# uOsc_1_v3.net
KiCad netlist of a schematic drawn in EAGLE
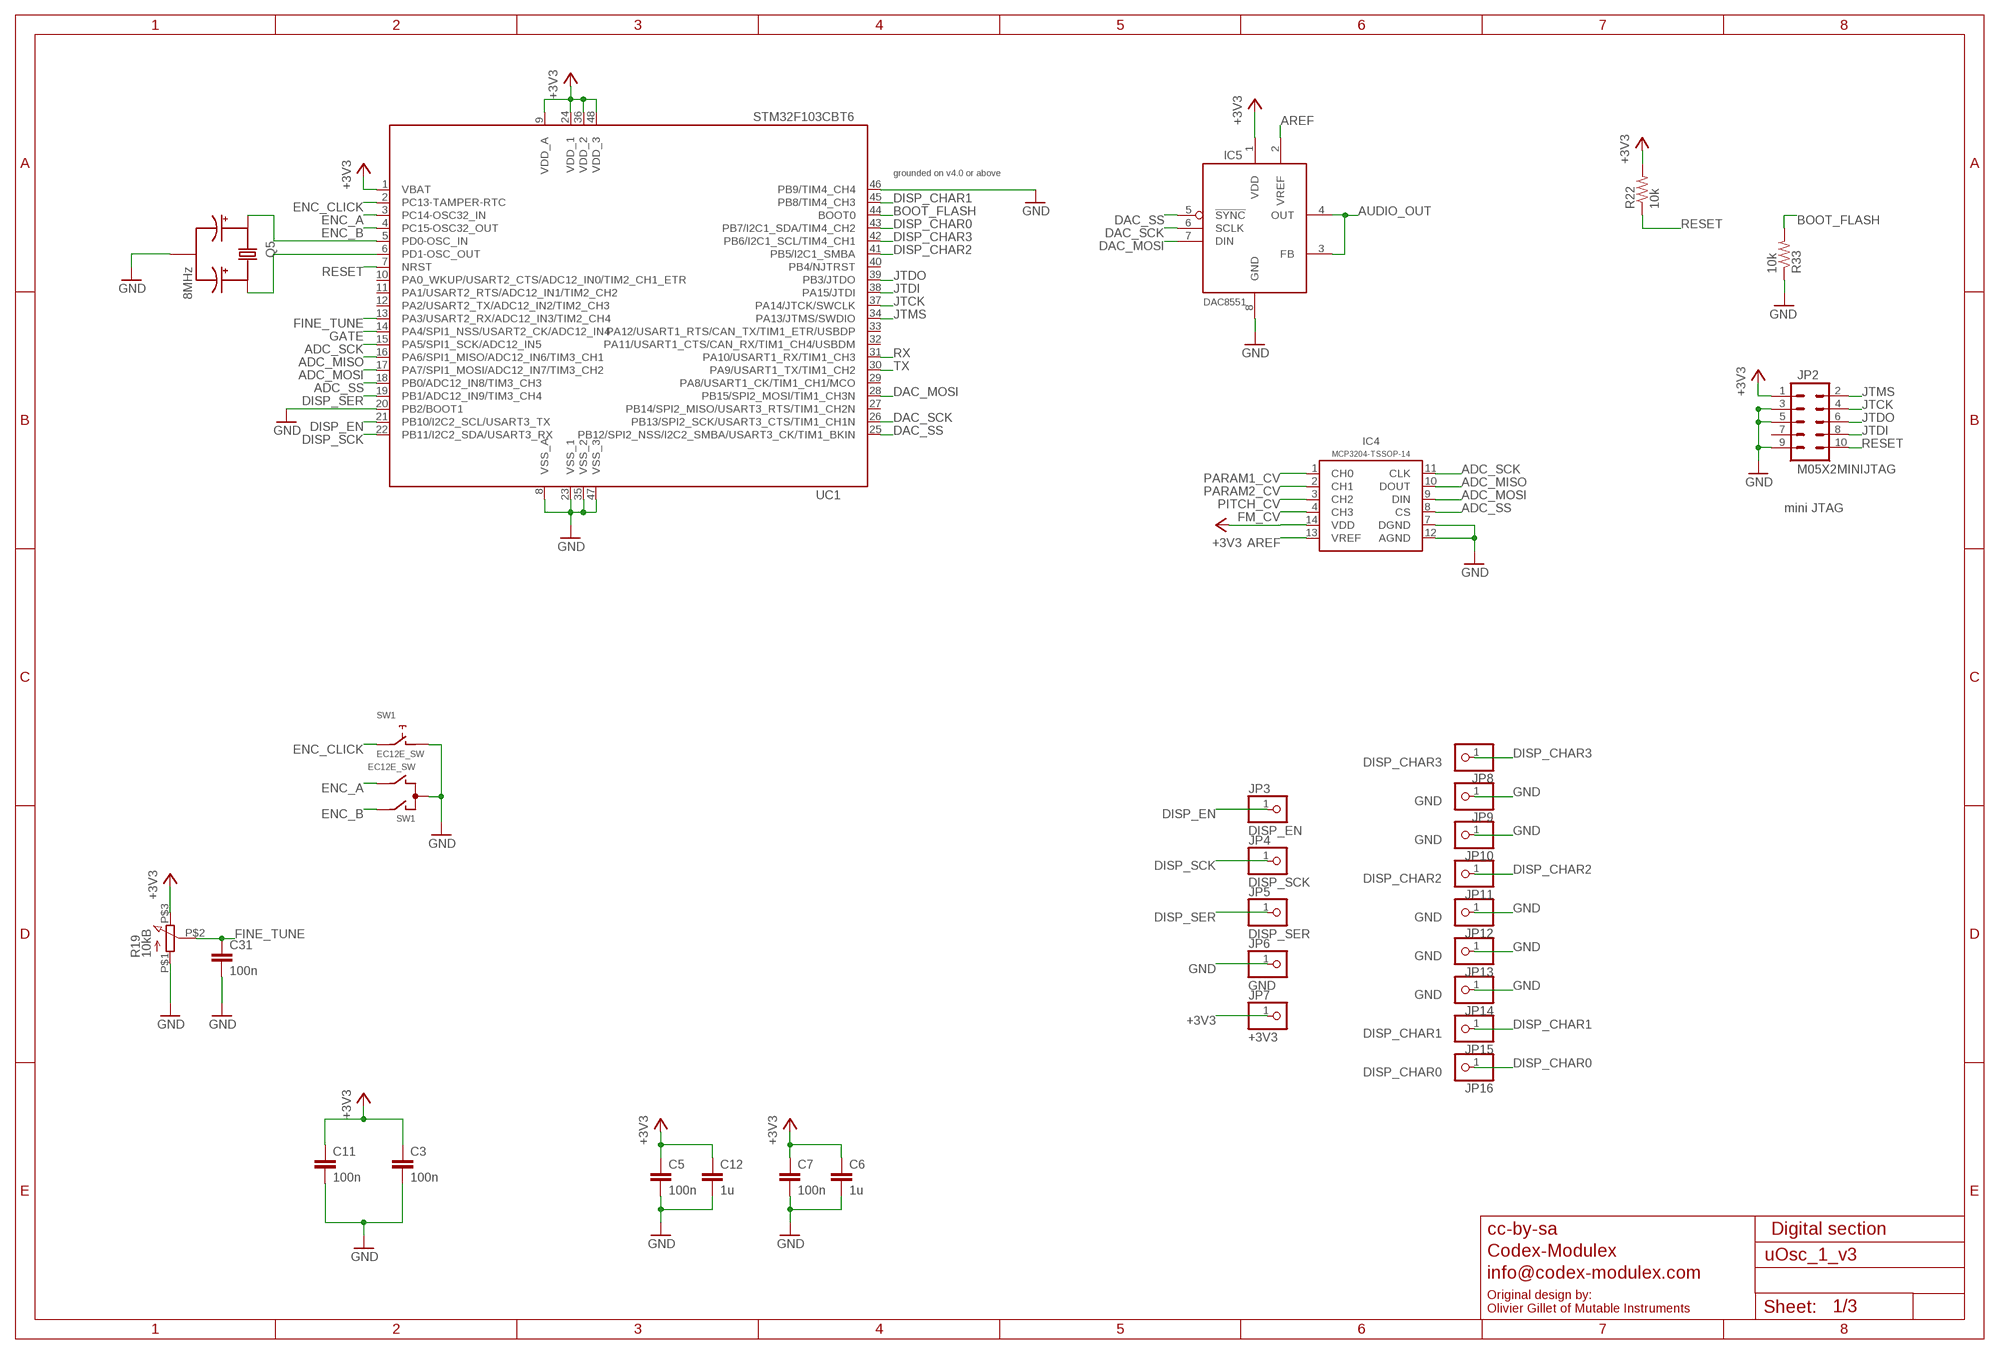
[diagram p0: schematic, sheet 1]
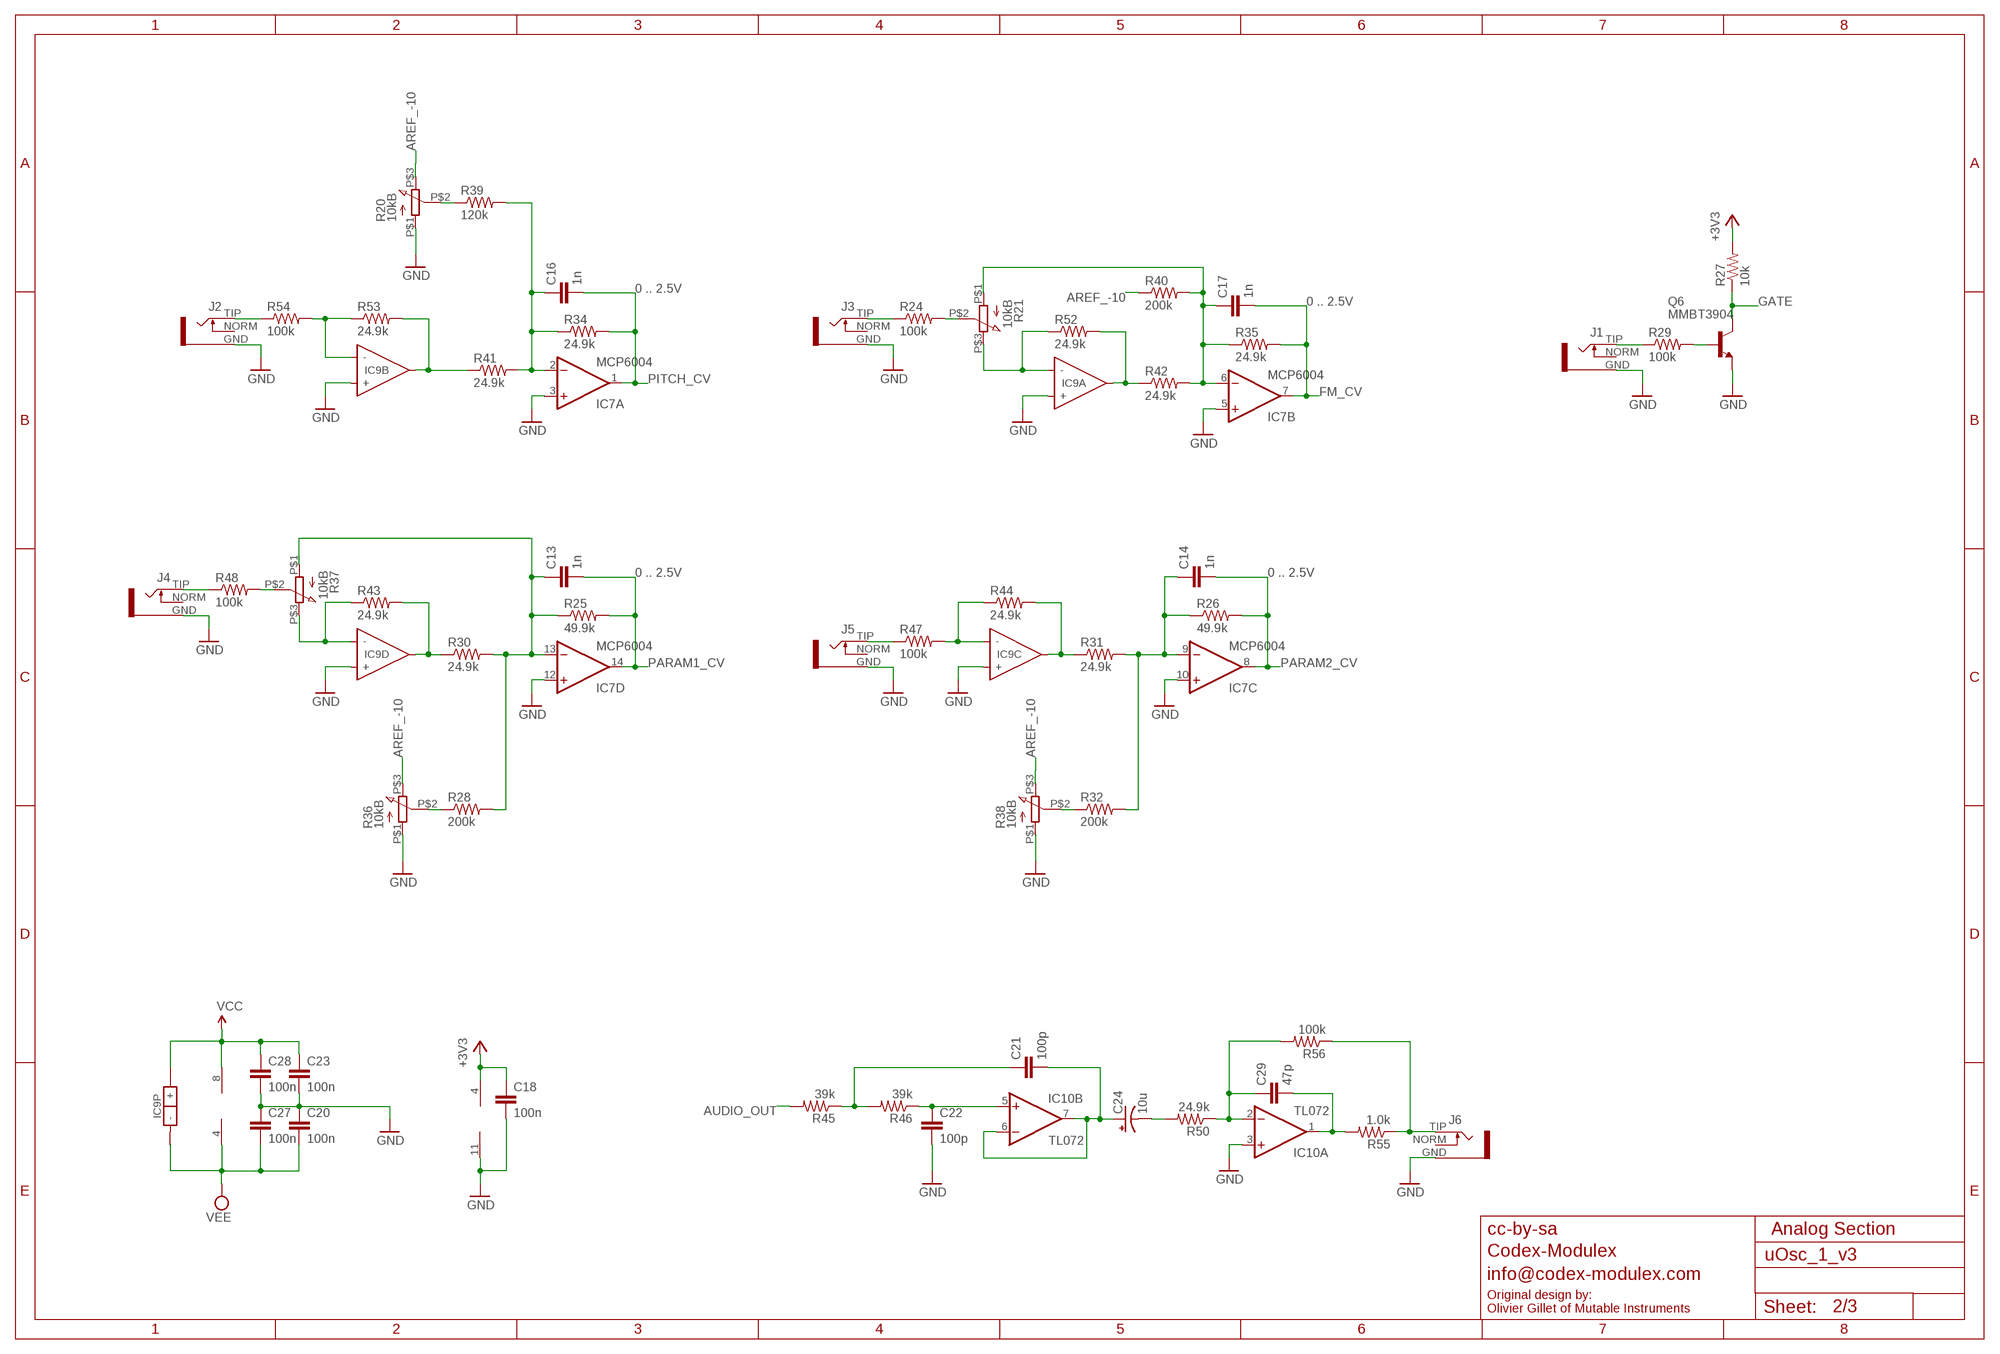
[diagram p1: schematic, sheet 2]
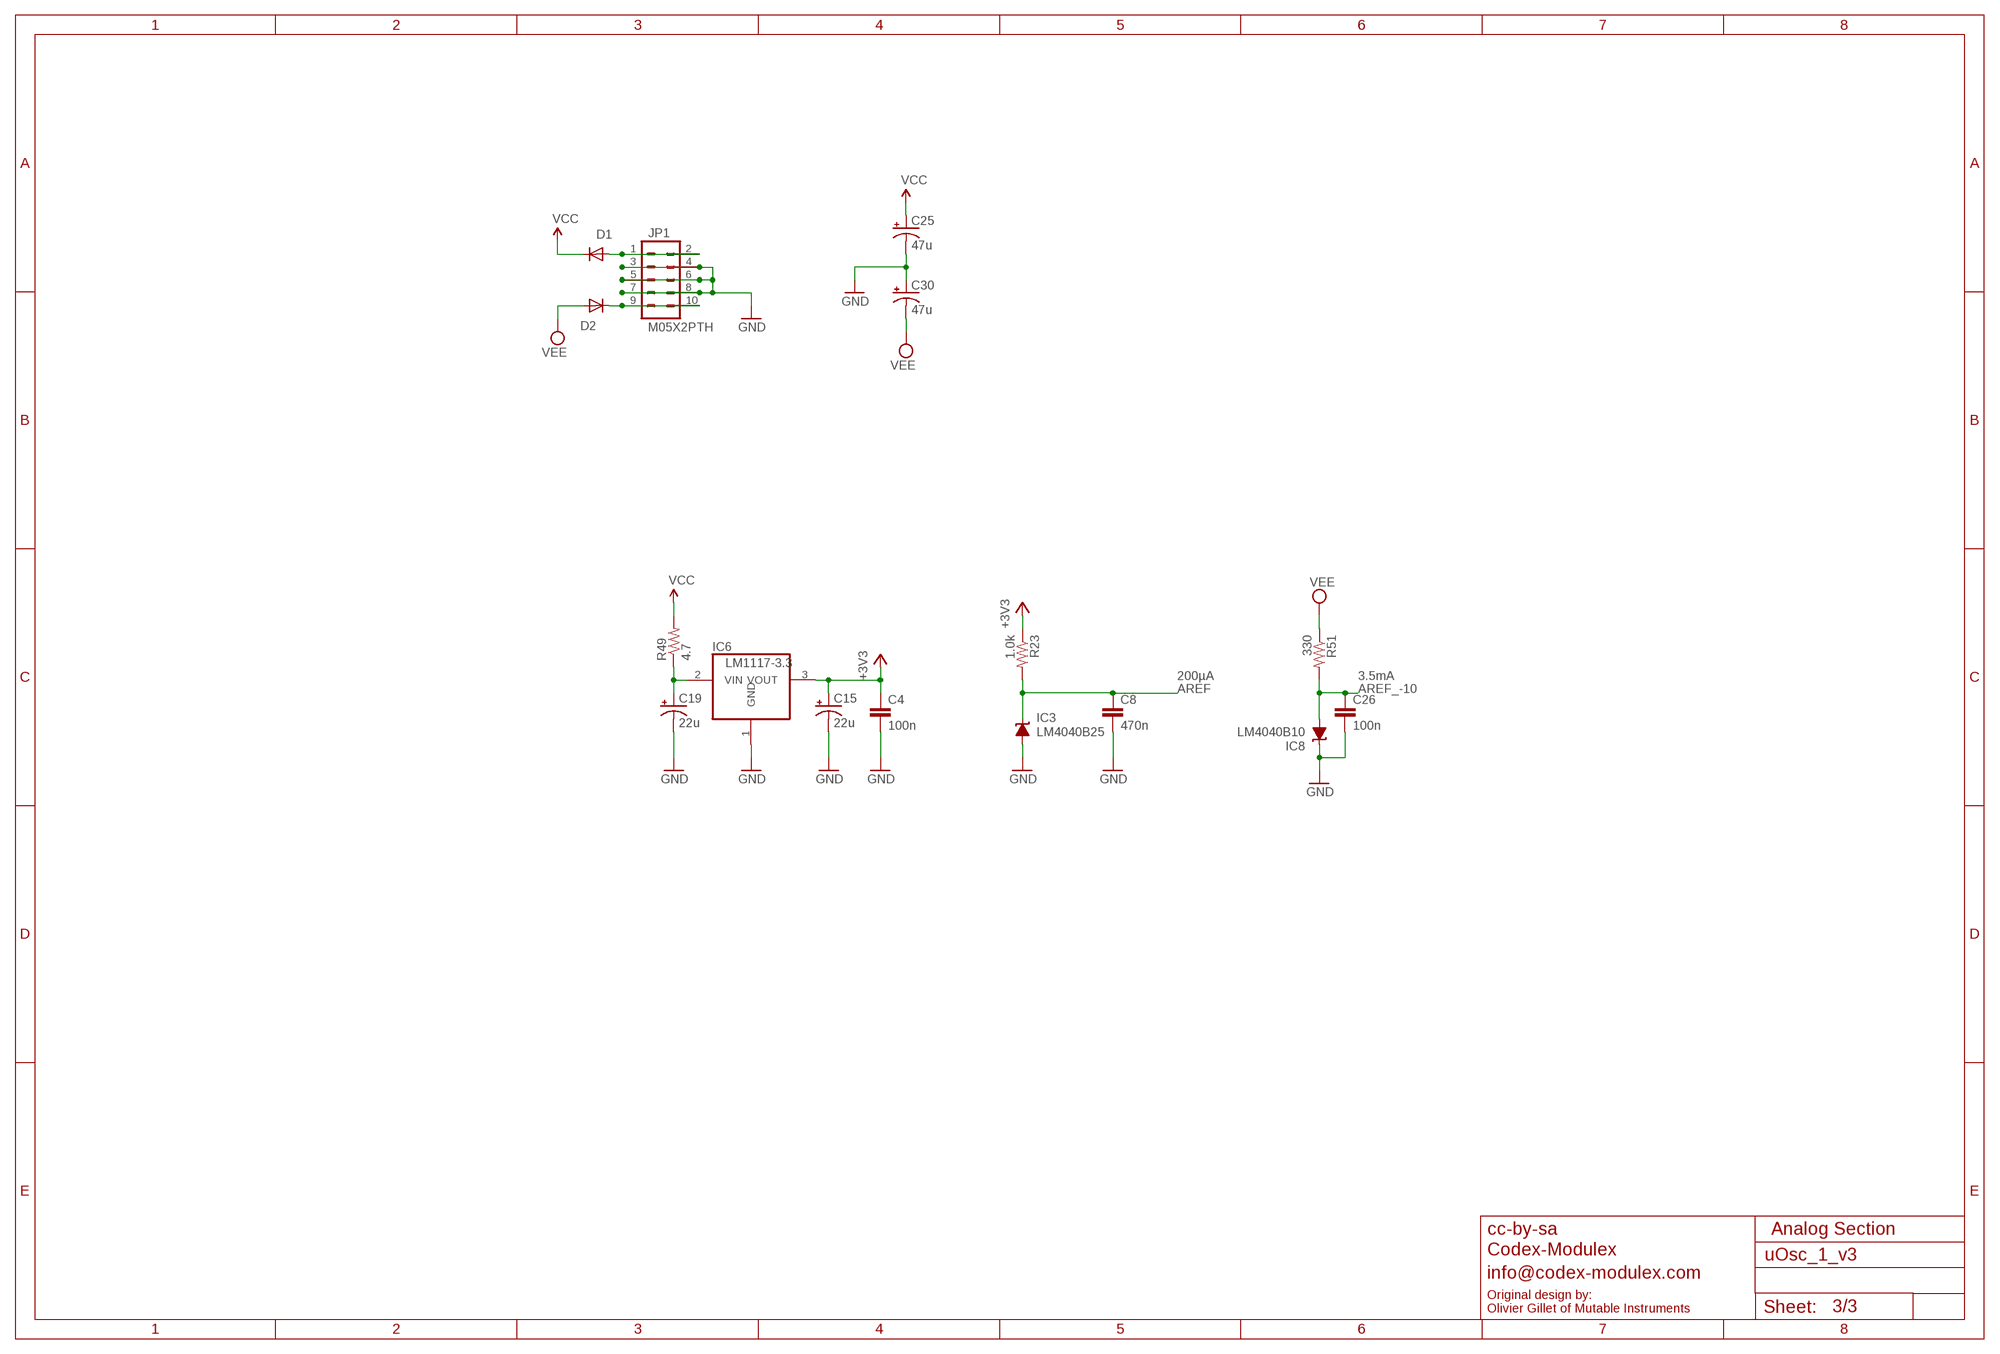
[diagram p2: schematic, sheet 3]

(export (version "E")
  (design (tool "Eeschema 10.0.6"))
  (components
    (comp (ref "C4")
      (value "100n")
      (footprint "eagle-import:PARTS_AMAN_RESISTOR_0603")
      (libsource (lib "eagle-import") (part "PARTS_AMAN_CAPACITOR"))
    )
    (comp (ref "C8")
      (value "470n")
      (footprint "eagle-import:PARTS_AMAN_RESISTOR_0603")
      (libsource (lib "eagle-import") (part "PARTS_AMAN_CAPACITOR"))
    )
    (comp (ref "C15")
      (value "22u")
      (footprint "eagle-import:PANASONIC_C")
      (libsource (lib "eagle-import") (part "CPOL-USC"))
    )
    (comp (ref "C19")
      (value "22u")
      (footprint "eagle-import:PANASONIC_C")
      (libsource (lib "eagle-import") (part "CPOL-USC"))
    )
    (comp (ref "C25")
      (value "47u")
      (footprint "eagle-import:PANASONIC_D")
      (libsource (lib "eagle-import") (part "CPOL-USD"))
    )
    (comp (ref "C26")
      (value "100n")
      (footprint "eagle-import:PARTS_AMAN_RESISTOR_0603")
      (libsource (lib "eagle-import") (part "PARTS_AMAN_CAPACITOR"))
    )
    (comp (ref "C30")
      (value "47u")
      (footprint "eagle-import:PANASONIC_D")
      (libsource (lib "eagle-import") (part "CPOL-USD"))
    )
    (comp (ref "D1")
      (value "1N5819HW")
      (footprint "eagle-import:SOD123")
      (libsource (lib "eagle-import") (part "DIODE-SOD123"))
    )
    (comp (ref "D2")
      (value "1N5819HW")
      (footprint "eagle-import:SOD123")
      (libsource (lib "eagle-import") (part "DIODE-SOD123"))
    )
    (comp (ref "IC3")
      (value "LM4040B25")
      (footprint "eagle-import:DBZ_R-PDSO-G3")
      (libsource (lib "eagle-import") (part "LM4041DBZB12"))
    )
    (comp (ref "IC6")
      (value "LM1117-3.3")
      (footprint "eagle-import:TO252")
      (libsource (lib "eagle-import") (part "REG1117T"))
    )
    (comp (ref "IC8")
      (value "LM4040B10")
      (footprint "eagle-import:DBZ_R-PDSO-G3")
      (libsource (lib "eagle-import") (part "LM4041DBZB12"))
    )
    (comp (ref "JP1")
      (value "M05X2PTH")
      (footprint "eagle-import:AVR_ICSP")
      (libsource (lib "eagle-import") (part "M05X2PTH"))
    )
    (comp (ref "R23")
      (value "1.0k")
      (footprint "eagle-import:PARTS_AMAN_RESISTOR_0603")
      (libsource (lib "eagle-import") (part "PARTS_AMAN_RESISTOR"))
    )
    (comp (ref "R49")
      (value "4.7")
      (footprint "eagle-import:R1206")
      (libsource (lib "eagle-import") (part "R-US_R1206"))
    )
    (comp (ref "R51")
      (value "330")
      (footprint "eagle-import:PARTS_AMAN_RESISTOR_0603")
      (libsource (lib "eagle-import") (part "PARTS_AMAN_RESISTOR"))
    )
    (comp (ref "C3")
      (value "100n")
      (footprint "eagle-import:PARTS_AMAN_RESISTOR_0603")
      (libsource (lib "eagle-import") (part "PARTS_AMAN_CAPACITOR"))
    )
    (comp (ref "C5")
      (value "100n")
      (footprint "eagle-import:PARTS_AMAN_RESISTOR_0603")
      (libsource (lib "eagle-import") (part "PARTS_AMAN_CAPACITOR"))
    )
    (comp (ref "C6")
      (value "1u")
      (footprint "eagle-import:PARTS_AMAN_RESISTOR_0603")
      (libsource (lib "eagle-import") (part "PARTS_AMAN_CAPACITOR"))
    )
    (comp (ref "C7")
      (value "100n")
      (footprint "eagle-import:PARTS_AMAN_RESISTOR_0603")
      (libsource (lib "eagle-import") (part "PARTS_AMAN_CAPACITOR"))
    )
    (comp (ref "C11")
      (value "100n")
      (footprint "eagle-import:PARTS_AMAN_RESISTOR_0603")
      (libsource (lib "eagle-import") (part "PARTS_AMAN_CAPACITOR"))
    )
    (comp (ref "C12")
      (value "1u")
      (footprint "eagle-import:PARTS_AMAN_RESISTOR_0603")
      (libsource (lib "eagle-import") (part "PARTS_AMAN_CAPACITOR"))
    )
    (comp (ref "C31")
      (value "100n")
      (footprint "eagle-import:PARTS_AMAN_RESISTOR_0603")
      (libsource (lib "eagle-import") (part "PARTS_AMAN_CAPACITOR"))
    )
    (comp (ref "IC4")
      (value "MCP3204-TSSOP-14")
      (footprint "eagle-import:UBRAIDS_SE_TSSOP-14")
      (libsource (lib "eagle-import") (part "UBRAIDS_SE_MCP3204-TSSOP-14"))
    )
    (comp (ref "IC5")
      (value "DAC8551")
      (footprint "eagle-import:MSOP-8")
      (libsource (lib "eagle-import") (part "DAC855X"))
    )
    (comp (ref "JP2")
      (value "M05X2MINIJTAG")
      (footprint "eagle-import:2X5-1.27")
      (libsource (lib "eagle-import") (part "M05X2MINIJTAG"))
    )
    (comp (ref "JP3")
      (value "DISP_EN")
      (footprint "eagle-import:PARTS_AMAN_1X01")
      (libsource (lib "eagle-import") (part "PARTS_AMAN_PINHD-1X1"))
    )
    (comp (ref "JP4")
      (value "DISP_SCK")
      (footprint "eagle-import:PARTS_AMAN_1X01")
      (libsource (lib "eagle-import") (part "PARTS_AMAN_PINHD-1X1"))
    )
    (comp (ref "JP5")
      (value "DISP_SER")
      (footprint "eagle-import:PARTS_AMAN_1X01")
      (libsource (lib "eagle-import") (part "PARTS_AMAN_PINHD-1X1"))
    )
    (comp (ref "JP6")
      (value "GND")
      (footprint "eagle-import:PARTS_AMAN_1X01")
      (libsource (lib "eagle-import") (part "PARTS_AMAN_PINHD-1X1"))
    )
    (comp (ref "JP7")
      (value "+3V3")
      (footprint "eagle-import:PARTS_AMAN_1X01")
      (libsource (lib "eagle-import") (part "PARTS_AMAN_PINHD-1X1"))
    )
    (comp (ref "JP8")
      (value "DISP_CHAR3")
      (footprint "eagle-import:PARTS_AMAN_1X01")
      (libsource (lib "eagle-import") (part "PARTS_AMAN_PINHD-1X1"))
    )
    (comp (ref "JP9")
      (value "GND")
      (footprint "eagle-import:PARTS_AMAN_1X01")
      (libsource (lib "eagle-import") (part "PARTS_AMAN_PINHD-1X1"))
    )
    (comp (ref "JP10")
      (value "GND")
      (footprint "eagle-import:PARTS_AMAN_1X01")
      (libsource (lib "eagle-import") (part "PARTS_AMAN_PINHD-1X1"))
    )
    (comp (ref "JP11")
      (value "DISP_CHAR2")
      (footprint "eagle-import:PARTS_AMAN_1X01")
      (libsource (lib "eagle-import") (part "PARTS_AMAN_PINHD-1X1"))
    )
    (comp (ref "JP12")
      (value "GND")
      (footprint "eagle-import:PARTS_AMAN_1X01")
      (libsource (lib "eagle-import") (part "PARTS_AMAN_PINHD-1X1"))
    )
    (comp (ref "JP13")
      (value "GND")
      (footprint "eagle-import:PARTS_AMAN_1X01")
      (libsource (lib "eagle-import") (part "PARTS_AMAN_PINHD-1X1"))
    )
    (comp (ref "JP14")
      (value "GND")
      (footprint "eagle-import:PARTS_AMAN_1X01")
      (libsource (lib "eagle-import") (part "PARTS_AMAN_PINHD-1X1"))
    )
    (comp (ref "JP15")
      (value "DISP_CHAR1")
      (footprint "eagle-import:PARTS_AMAN_1X01")
      (libsource (lib "eagle-import") (part "PARTS_AMAN_PINHD-1X1"))
    )
    (comp (ref "JP16")
      (value "DISP_CHAR0")
      (footprint "eagle-import:PARTS_AMAN_1X01")
      (libsource (lib "eagle-import") (part "PARTS_AMAN_PINHD-1X1"))
    )
    (comp (ref "Q5")
      (value "8MHz")
      (footprint "eagle-import:CRYSTAL_SMALLER")
      (libsource (lib "eagle-import") (part "CRYSTAL_SMALLER"))
    )
    (comp (ref "R19")
      (value "10kB")
      (footprint "eagle-import:Q-POT2")
      (libsource (lib "eagle-import") (part "Q-POT2"))
    )
    (comp (ref "R22")
      (value "10k")
      (footprint "eagle-import:PARTS_AMAN_RESISTOR_0603")
      (libsource (lib "eagle-import") (part "PARTS_AMAN_RESISTOR"))
    )
    (comp (ref "R33")
      (value "10k")
      (footprint "eagle-import:PARTS_AMAN_RESISTOR_0603")
      (libsource (lib "eagle-import") (part "PARTS_AMAN_RESISTOR"))
    )
    (comp (ref "SW1")
      (value "EC12E_SW")
      (footprint "eagle-import:ALPS_EC12E_SW")
      (libsource (lib "eagle-import") (part "EC12E_SW"))
    )
    (comp (ref "UC1")
      (value "STM32F103CBT6")
      (footprint "eagle-import:LQFP48")
      (libsource (lib "eagle-import") (part "STM32F103CB"))
    )
    (comp (ref "C13")
      (value "1n")
      (footprint "eagle-import:PARTS_AMAN_RESISTOR_0603")
      (libsource (lib "eagle-import") (part "PARTS_AMAN_CAPACITOR"))
    )
    (comp (ref "C14")
      (value "1n")
      (footprint "eagle-import:PARTS_AMAN_RESISTOR_0603")
      (libsource (lib "eagle-import") (part "PARTS_AMAN_CAPACITOR"))
    )
    (comp (ref "C16")
      (value "1n")
      (footprint "eagle-import:PARTS_AMAN_RESISTOR_0603")
      (libsource (lib "eagle-import") (part "PARTS_AMAN_CAPACITOR"))
    )
    (comp (ref "C17")
      (value "1n")
      (footprint "eagle-import:PARTS_AMAN_RESISTOR_0603")
      (libsource (lib "eagle-import") (part "PARTS_AMAN_CAPACITOR"))
    )
    (comp (ref "C18")
      (value "100n")
      (footprint "eagle-import:PARTS_AMAN_RESISTOR_0603")
      (libsource (lib "eagle-import") (part "PARTS_AMAN_CAPACITOR"))
    )
    (comp (ref "C20")
      (value "100n")
      (footprint "eagle-import:PARTS_AMAN_RESISTOR_0603")
      (libsource (lib "eagle-import") (part "PARTS_AMAN_CAPACITOR"))
    )
    (comp (ref "C21")
      (value "100p")
      (footprint "eagle-import:PARTS_AMAN_RESISTOR_0603")
      (libsource (lib "eagle-import") (part "PARTS_AMAN_CAPACITOR"))
    )
    (comp (ref "C22")
      (value "100p")
      (footprint "eagle-import:PARTS_AMAN_RESISTOR_0603")
      (libsource (lib "eagle-import") (part "PARTS_AMAN_CAPACITOR"))
    )
    (comp (ref "C23")
      (value "100n")
      (footprint "eagle-import:PARTS_AMAN_RESISTOR_0603")
      (libsource (lib "eagle-import") (part "PARTS_AMAN_CAPACITOR"))
    )
    (comp (ref "C24")
      (value "10u")
      (footprint "eagle-import:PANASONIC_B")
      (libsource (lib "eagle-import") (part "CPOL-USB"))
    )
    (comp (ref "C27")
      (value "100n")
      (footprint "eagle-import:PARTS_AMAN_RESISTOR_0603")
      (libsource (lib "eagle-import") (part "PARTS_AMAN_CAPACITOR"))
    )
    (comp (ref "C28")
      (value "100n")
      (footprint "eagle-import:PARTS_AMAN_RESISTOR_0603")
      (libsource (lib "eagle-import") (part "PARTS_AMAN_CAPACITOR"))
    )
    (comp (ref "C29")
      (value "47p")
      (footprint "eagle-import:PARTS_AMAN_RESISTOR_0603")
      (libsource (lib "eagle-import") (part "PARTS_AMAN_CAPACITOR"))
    )
    (comp (ref "IC7")
      (value "MCP6004")
      (footprint "eagle-import:SO14")
      (libsource (lib "eagle-import") (part "TL074D"))
    )
    (comp (ref "IC9")
      (value "TL074")
      (footprint "eagle-import:UBRAIDS_SE_TSSOP-14")
      (libsource (lib "eagle-import") (part "UBRAIDS_SE_TL074-TSSOP-14"))
    )
    (comp (ref "IC10")
      (value "TL072")
      (footprint "eagle-import:SO08")
      (libsource (lib "eagle-import") (part "TL072D"))
    )
    (comp (ref "J1")
      (value "S_JACK_S2_INV")
      (footprint "eagle-import:S_JACK_S2_INV")
      (libsource (lib "eagle-import") (part "S_JACK_S2_INV"))
    )
    (comp (ref "J2")
      (value "S_JACK_S2_INV")
      (footprint "eagle-import:S_JACK_S2_INV")
      (libsource (lib "eagle-import") (part "S_JACK_S2_INV"))
    )
    (comp (ref "J3")
      (value "S_JACK_S2_INV")
      (footprint "eagle-import:S_JACK_S2_INV")
      (libsource (lib "eagle-import") (part "S_JACK_S2_INV"))
    )
    (comp (ref "J4")
      (value "S_JACK_S2_INV")
      (footprint "eagle-import:S_JACK_S2_INV")
      (libsource (lib "eagle-import") (part "S_JACK_S2_INV"))
    )
    (comp (ref "J5")
      (value "S_JACK_S2_INV")
      (footprint "eagle-import:S_JACK_S2_INV")
      (libsource (lib "eagle-import") (part "S_JACK_S2_INV"))
    )
    (comp (ref "J6")
      (value "S_JACK_S2_INV")
      (footprint "eagle-import:S_JACK_S2_INV")
      (libsource (lib "eagle-import") (part "S_JACK_S2_INV"))
    )
    (comp (ref "Q6")
      (value "MMBT3904")
      (footprint "eagle-import:SOT23-BEC")
      (libsource (lib "eagle-import") (part "-NPN-SOT23-BECMMBT3904LT1"))
    )
    (comp (ref "R20")
      (value "10kB")
      (footprint "eagle-import:Q-POT2")
      (libsource (lib "eagle-import") (part "Q-POT2"))
    )
    (comp (ref "R21")
      (value "10kB")
      (footprint "eagle-import:Q-POT2")
      (libsource (lib "eagle-import") (part "Q-POT2"))
    )
    (comp (ref "R24")
      (value "100k")
      (footprint "eagle-import:PARTS_AMAN_RESISTOR_0603")
      (libsource (lib "eagle-import") (part "PARTS_AMAN_RESISTOR"))
    )
    (comp (ref "R25")
      (value "49.9k")
      (footprint "eagle-import:PARTS_AMAN_RESISTOR_0603")
      (libsource (lib "eagle-import") (part "PARTS_AMAN_RESISTOR"))
    )
    (comp (ref "R26")
      (value "49.9k")
      (footprint "eagle-import:PARTS_AMAN_RESISTOR_0603")
      (libsource (lib "eagle-import") (part "PARTS_AMAN_RESISTOR"))
    )
    (comp (ref "R27")
      (value "10k")
      (footprint "eagle-import:PARTS_AMAN_RESISTOR_0603")
      (libsource (lib "eagle-import") (part "PARTS_AMAN_RESISTOR"))
    )
    (comp (ref "R28")
      (value "200k")
      (footprint "eagle-import:PARTS_AMAN_RESISTOR_0603")
      (libsource (lib "eagle-import") (part "PARTS_AMAN_RESISTOR"))
    )
    (comp (ref "R29")
      (value "100k")
      (footprint "eagle-import:PARTS_AMAN_RESISTOR_0603")
      (libsource (lib "eagle-import") (part "PARTS_AMAN_RESISTOR"))
    )
    (comp (ref "R30")
      (value "24.9k")
      (footprint "eagle-import:PARTS_AMAN_RESISTOR_0603")
      (libsource (lib "eagle-import") (part "PARTS_AMAN_RESISTOR"))
    )
    (comp (ref "R31")
      (value "24.9k")
      (footprint "eagle-import:PARTS_AMAN_RESISTOR_0603")
      (libsource (lib "eagle-import") (part "PARTS_AMAN_RESISTOR"))
    )
    (comp (ref "R32")
      (value "200k")
      (footprint "eagle-import:PARTS_AMAN_RESISTOR_0603")
      (libsource (lib "eagle-import") (part "PARTS_AMAN_RESISTOR"))
    )
    (comp (ref "R34")
      (value "24.9k")
      (footprint "eagle-import:PARTS_AMAN_RESISTOR_0603")
      (libsource (lib "eagle-import") (part "PARTS_AMAN_RESISTOR"))
    )
    (comp (ref "R35")
      (value "24.9k")
      (footprint "eagle-import:PARTS_AMAN_RESISTOR_0603")
      (libsource (lib "eagle-import") (part "PARTS_AMAN_RESISTOR"))
    )
    (comp (ref "R36")
      (value "10kB")
      (footprint "eagle-import:Q-POT2")
      (libsource (lib "eagle-import") (part "Q-POT2"))
    )
    (comp (ref "R37")
      (value "10kB")
      (footprint "eagle-import:Q-POT2")
      (libsource (lib "eagle-import") (part "Q-POT2"))
    )
    (comp (ref "R38")
      (value "10kB")
      (footprint "eagle-import:Q-POT2")
      (libsource (lib "eagle-import") (part "Q-POT2"))
    )
    (comp (ref "R39")
      (value "120k")
      (footprint "eagle-import:PARTS_AMAN_RESISTOR_0603")
      (libsource (lib "eagle-import") (part "PARTS_AMAN_RESISTOR"))
    )
    (comp (ref "R40")
      (value "200k")
      (footprint "eagle-import:PARTS_AMAN_RESISTOR_0603")
      (libsource (lib "eagle-import") (part "PARTS_AMAN_RESISTOR"))
    )
    (comp (ref "R41")
      (value "24.9k")
      (footprint "eagle-import:PARTS_AMAN_RESISTOR_0603")
      (libsource (lib "eagle-import") (part "PARTS_AMAN_RESISTOR"))
    )
    (comp (ref "R42")
      (value "24.9k")
      (footprint "eagle-import:PARTS_AMAN_RESISTOR_0603")
      (libsource (lib "eagle-import") (part "PARTS_AMAN_RESISTOR"))
    )
    (comp (ref "R43")
      (value "24.9k")
      (footprint "eagle-import:PARTS_AMAN_RESISTOR_0603")
      (libsource (lib "eagle-import") (part "PARTS_AMAN_RESISTOR"))
    )
    (comp (ref "R44")
      (value "24.9k")
      (footprint "eagle-import:PARTS_AMAN_RESISTOR_0603")
      (libsource (lib "eagle-import") (part "PARTS_AMAN_RESISTOR"))
    )
    (comp (ref "R45")
      (value "39k")
      (footprint "eagle-import:PARTS_AMAN_RESISTOR_0603")
      (libsource (lib "eagle-import") (part "PARTS_AMAN_RESISTOR"))
    )
    (comp (ref "R46")
      (value "39k")
      (footprint "eagle-import:PARTS_AMAN_RESISTOR_0603")
      (libsource (lib "eagle-import") (part "PARTS_AMAN_RESISTOR"))
    )
    (comp (ref "R47")
      (value "100k")
      (footprint "eagle-import:PARTS_AMAN_RESISTOR_0603")
      (libsource (lib "eagle-import") (part "PARTS_AMAN_RESISTOR"))
    )
    (comp (ref "R48")
      (value "100k")
      (footprint "eagle-import:PARTS_AMAN_RESISTOR_0603")
      (libsource (lib "eagle-import") (part "PARTS_AMAN_RESISTOR"))
    )
    (comp (ref "R50")
      (value "24.9k")
      (footprint "eagle-import:PARTS_AMAN_RESISTOR_0603")
      (libsource (lib "eagle-import") (part "PARTS_AMAN_RESISTOR"))
    )
    (comp (ref "R52")
      (value "24.9k")
      (footprint "eagle-import:PARTS_AMAN_RESISTOR_0603")
      (libsource (lib "eagle-import") (part "PARTS_AMAN_RESISTOR"))
    )
    (comp (ref "R53")
      (value "24.9k")
      (footprint "eagle-import:PARTS_AMAN_RESISTOR_0603")
      (libsource (lib "eagle-import") (part "PARTS_AMAN_RESISTOR"))
    )
    (comp (ref "R54")
      (value "100k")
      (footprint "eagle-import:PARTS_AMAN_RESISTOR_0603")
      (libsource (lib "eagle-import") (part "PARTS_AMAN_RESISTOR"))
    )
    (comp (ref "R55")
      (value "1.0k")
      (footprint "eagle-import:PARTS_AMAN_RESISTOR_0603")
      (libsource (lib "eagle-import") (part "PARTS_AMAN_RESISTOR"))
    )
    (comp (ref "R56")
      (value "100k")
      (footprint "eagle-import:PARTS_AMAN_RESISTOR_0603")
      (libsource (lib "eagle-import") (part "PARTS_AMAN_RESISTOR"))
    )
  )
  (nets
    (net (code "1") (name "+3V3") (class "Default")
      (node (ref "C11") (pin "1") (pinfunction "1_1") (pintype "passive"))
      (node (ref "C12") (pin "1") (pinfunction "1_1") (pintype "passive"))
      (node (ref "C15") (pin "+") (pinfunction "+_+") (pintype "passive"))
      (node (ref "C18") (pin "1") (pinfunction "1_1") (pintype "passive"))
      (node (ref "C3") (pin "1") (pinfunction "1_1") (pintype "passive"))
      (node (ref "C4") (pin "1") (pinfunction "1_1") (pintype "passive"))
      (node (ref "C5") (pin "1") (pinfunction "1_1") (pintype "passive"))
      (node (ref "C6") (pin "1") (pinfunction "1_1") (pintype "passive"))
      (node (ref "C7") (pin "1") (pinfunction "1_1") (pintype "passive"))
      (node (ref "IC4") (pin "14") (pinfunction "VDD_14") (pintype "bidirectional"))
      (node (ref "IC5") (pin "1") (pinfunction "VDD_1") (pintype "power_in"))
      (node (ref "IC6") (pin "3") (pinfunction "VOUT_3") (pintype "output"))
      (node (ref "IC7") (pin "4") (pinfunction "V+_4") (pintype "power_in"))
      (node (ref "JP2") (pin "1") (pinfunction "1_1") (pintype "passive"))
      (node (ref "JP7") (pin "1") (pinfunction "1_1") (pintype "passive"))
      (node (ref "R19") (pin "P$3") (pinfunction "3_P$3") (pintype "passive"))
      (node (ref "R22") (pin "2") (pinfunction "2_2") (pintype "passive"))
      (node (ref "R23") (pin "1") (pinfunction "1_1") (pintype "passive"))
      (node (ref "R27") (pin "2") (pinfunction "2_2") (pintype "passive"))
      (node (ref "UC1") (pin "1") (pinfunction "VBAT_1") (pintype "power_in"))
      (node (ref "UC1") (pin "24") (pinfunction "VDD_1_24") (pintype "power_in"))
      (node (ref "UC1") (pin "36") (pinfunction "VDD_2_36") (pintype "power_in"))
      (node (ref "UC1") (pin "48") (pinfunction "VDD_3_48") (pintype "power_in"))
      (node (ref "UC1") (pin "9") (pinfunction "VDD_A_9") (pintype "power_in"))
    )
    (net (code "2") (name "ADC_MISO") (class "Default")
      (node (ref "IC4") (pin "10") (pinfunction "DOUT_10") (pintype "bidirectional"))
      (node (ref "UC1") (pin "16") (pinfunction "PA6/SPI1_MISO/ADC12_IN6/TIM3_CH1_16") (pintype "bidirectional"))
    )
    (net (code "3") (name "ADC_MOSI") (class "Default")
      (node (ref "IC4") (pin "9") (pinfunction "DIN_9") (pintype "bidirectional"))
      (node (ref "UC1") (pin "17") (pinfunction "PA7/SPI1_MOSI/ADC12_IN7/TIM3_CH2_17") (pintype "bidirectional"))
    )
    (net (code "4") (name "ADC_SCK") (class "Default")
      (node (ref "IC4") (pin "11") (pinfunction "CLK_11") (pintype "bidirectional"))
      (node (ref "UC1") (pin "15") (pinfunction "PA5/SPI1_SCK/ADC12_IN5_15") (pintype "bidirectional"))
    )
    (net (code "5") (name "ADC_SS") (class "Default")
      (node (ref "IC4") (pin "8") (pinfunction "CS_8") (pintype "bidirectional"))
      (node (ref "UC1") (pin "18") (pinfunction "PB0/ADC12_IN8/TIM3_CH3_18") (pintype "bidirectional"))
    )
    (net (code "6") (name "AREF") (class "Default")
      (node (ref "C8") (pin "1") (pinfunction "1_1") (pintype "passive"))
      (node (ref "IC3") (pin "1") (pinfunction "C_1") (pintype "passive"))
      (node (ref "IC4") (pin "13") (pinfunction "VREF_13") (pintype "bidirectional"))
      (node (ref "IC5") (pin "2") (pinfunction "VREF_2") (pintype "power_in"))
      (node (ref "R23") (pin "2") (pinfunction "2_2") (pintype "passive"))
    )
    (net (code "7") (name "AREF_-10") (class "Default")
      (node (ref "C26") (pin "1") (pinfunction "1_1") (pintype "passive"))
      (node (ref "IC8") (pin "2") (pinfunction "A_2") (pintype "passive"))
      (node (ref "R20") (pin "P$3") (pinfunction "3_P$3") (pintype "passive"))
      (node (ref "R36") (pin "P$3") (pinfunction "3_P$3") (pintype "passive"))
      (node (ref "R38") (pin "P$3") (pinfunction "3_P$3") (pintype "passive"))
      (node (ref "R40") (pin "1") (pinfunction "1_1") (pintype "passive"))
      (node (ref "R51") (pin "2") (pinfunction "2_2") (pintype "passive"))
    )
    (net (code "8") (name "AUDIO_OUT") (class "Default")
      (node (ref "IC5") (pin "3") (pinfunction "FB_3") (pintype "input"))
      (node (ref "IC5") (pin "4") (pinfunction "OUT_4") (pintype "output"))
      (node (ref "R45") (pin "2") (pinfunction "2_2") (pintype "passive"))
    )
    (net (code "9") (name "BOOT_FLASH") (class "Default")
      (node (ref "R33") (pin "2") (pinfunction "2_2") (pintype "passive"))
      (node (ref "UC1") (pin "44") (pinfunction "BOOT0_44") (pintype "input"))
    )
    (net (code "10") (name "DAC_MOSI") (class "Default")
      (node (ref "IC5") (pin "7") (pinfunction "DIN_7") (pintype "bidirectional"))
      (node (ref "UC1") (pin "28") (pinfunction "PB15/SPI2_MOSI/TIM1_CH3N_28") (pintype "input"))
    )
    (net (code "11") (name "DAC_SCK") (class "Default")
      (node (ref "IC5") (pin "6") (pinfunction "SCLK_6") (pintype "bidirectional"))
      (node (ref "UC1") (pin "26") (pinfunction "PB13/SPI2_SCK/USART3_CTS/TIM1_CH1N_26") (pintype "input"))
    )
    (net (code "12") (name "DAC_SS") (class "Default")
      (node (ref "IC5") (pin "5") (pinfunction "~{SYNC}_5") (pintype "bidirectional"))
      (node (ref "UC1") (pin "25") (pinfunction "PB12/SPI2_NSS/I2C2_SMBA/USART3_CK/TIM1_BKIN_25") (pintype "input"))
    )
    (net (code "13") (name "DISP_CHAR0") (class "Default")
      (node (ref "JP16") (pin "1") (pinfunction "1_1") (pintype "passive"))
      (node (ref "UC1") (pin "43") (pinfunction "PB7/I2C1_SDA/TIM4_CH2_43") (pintype "bidirectional"))
    )
    (net (code "14") (name "DISP_CHAR1") (class "Default")
      (node (ref "JP15") (pin "1") (pinfunction "1_1") (pintype "passive"))
      (node (ref "UC1") (pin "45") (pinfunction "PB8/TIM4_CH3_45") (pintype "bidirectional"))
    )
    (net (code "15") (name "DISP_CHAR2") (class "Default")
      (node (ref "JP11") (pin "1") (pinfunction "1_1") (pintype "passive"))
      (node (ref "UC1") (pin "41") (pinfunction "PB5/I2C1_SMBA_41") (pintype "input"))
    )
    (net (code "16") (name "DISP_CHAR3") (class "Default")
      (node (ref "JP8") (pin "1") (pinfunction "1_1") (pintype "passive"))
      (node (ref "UC1") (pin "42") (pinfunction "PB6/I2C1_SCL/TIM4_CH1_42") (pintype "input"))
    )
    (net (code "17") (name "DISP_EN") (class "Default")
      (node (ref "JP3") (pin "1") (pinfunction "1_1") (pintype "passive"))
      (node (ref "UC1") (pin "21") (pinfunction "PB10/I2C2_SCL/USART3_TX_21") (pintype "input"))
    )
    (net (code "18") (name "DISP_SCK") (class "Default")
      (node (ref "JP4") (pin "1") (pinfunction "1_1") (pintype "passive"))
      (node (ref "UC1") (pin "22") (pinfunction "PB11/I2C2_SDA/USART3_RX_22") (pintype "input"))
    )
    (net (code "19") (name "DISP_SER") (class "Default")
      (node (ref "JP5") (pin "1") (pinfunction "1_1") (pintype "passive"))
      (node (ref "UC1") (pin "19") (pinfunction "PB1/ADC12_IN9/TIM3_CH4_19") (pintype "bidirectional"))
    )
    (net (code "20") (name "ENC_A") (class "Default")
      (node (ref "SW1") (pin "B") (pinfunction "B_B") (pintype "passive"))
      (node (ref "UC1") (pin "3") (pinfunction "PC14-OSC32_IN_3") (pintype "input"))
    )
    (net (code "21") (name "ENC_B") (class "Default")
      (node (ref "SW1") (pin "A") (pinfunction "A_A") (pintype "passive"))
      (node (ref "UC1") (pin "4") (pinfunction "PC15-OSC32_OUT_4") (pintype "input"))
    )
    (net (code "22") (name "ENC_CLICK") (class "Default")
      (node (ref "SW1") (pin "E") (pinfunction "2_E") (pintype "passive"))
      (node (ref "UC1") (pin "2") (pinfunction "PC13-TAMPER-RTC_2") (pintype "input"))
    )
    (net (code "23") (name "FINE_TUNE") (class "Default")
      (node (ref "C31") (pin "1") (pinfunction "1_1") (pintype "passive"))
      (node (ref "R19") (pin "P$2") (pinfunction "2_P$2") (pintype "passive"))
      (node (ref "UC1") (pin "13") (pinfunction "PA3/USART2_RX/ADC12_IN3/TIM2_CH4_13") (pintype "bidirectional"))
    )
    (net (code "24") (name "FM_CV") (class "Default")
      (node (ref "C17") (pin "2") (pinfunction "2_2") (pintype "passive"))
      (node (ref "IC4") (pin "4") (pinfunction "CH3_4") (pintype "bidirectional"))
      (node (ref "IC7") (pin "7") (pinfunction "OUT_7") (pintype "output"))
      (node (ref "R35") (pin "2") (pinfunction "2_2") (pintype "passive"))
    )
    (net (code "25") (name "GATE") (class "Default")
      (node (ref "Q6") (pin "C") (pinfunction "C_C") (pintype "passive"))
      (node (ref "R27") (pin "1") (pinfunction "1_1") (pintype "passive"))
      (node (ref "UC1") (pin "14") (pinfunction "PA4/SPI1_NSS/USART2_CK/ADC12_IN4_14") (pintype "bidirectional"))
    )
    (net (code "26") (name "GND") (class "Default")
      (node (ref "C11") (pin "2") (pinfunction "2_2") (pintype "passive"))
      (node (ref "C12") (pin "2") (pinfunction "2_2") (pintype "passive"))
      (node (ref "C15") (pin "-") (pinfunction "-_-") (pintype "passive"))
      (node (ref "C18") (pin "2") (pinfunction "2_2") (pintype "passive"))
      (node (ref "C19") (pin "-") (pinfunction "-_-") (pintype "passive"))
      (node (ref "C20") (pin "1") (pinfunction "1_1") (pintype "passive"))
      (node (ref "C22") (pin "2") (pinfunction "2_2") (pintype "passive"))
      (node (ref "C23") (pin "2") (pinfunction "2_2") (pintype "passive"))
      (node (ref "C25") (pin "-") (pinfunction "-_-") (pintype "passive"))
      (node (ref "C26") (pin "2") (pinfunction "2_2") (pintype "passive"))
      (node (ref "C27") (pin "1") (pinfunction "1_1") (pintype "passive"))
      (node (ref "C28") (pin "2") (pinfunction "2_2") (pintype "passive"))
      (node (ref "C3") (pin "2") (pinfunction "2_2") (pintype "passive"))
      (node (ref "C30") (pin "+") (pinfunction "+_+") (pintype "passive"))
      (node (ref "C31") (pin "2") (pinfunction "2_2") (pintype "passive"))
      (node (ref "C4") (pin "2") (pinfunction "2_2") (pintype "passive"))
      (node (ref "C5") (pin "2") (pinfunction "2_2") (pintype "passive"))
      (node (ref "C6") (pin "2") (pinfunction "2_2") (pintype "passive"))
      (node (ref "C7") (pin "2") (pinfunction "2_2") (pintype "passive"))
      (node (ref "C8") (pin "2") (pinfunction "2_2") (pintype "passive"))
      (node (ref "IC10") (pin "3") (pinfunction "+IN_3") (pintype "input"))
      (node (ref "IC3") (pin "2") (pinfunction "A_2") (pintype "passive"))
      (node (ref "IC4") (pin "12") (pinfunction "AGND_12") (pintype "bidirectional"))
      (node (ref "IC4") (pin "7") (pinfunction "DGND_7") (pintype "bidirectional"))
      (node (ref "IC5") (pin "8") (pinfunction "GND_8") (pintype "power_in"))
      (node (ref "IC6") (pin "1") (pinfunction "GND_1") (pintype "power_in"))
      (node (ref "IC7") (pin "10") (pinfunction "+IN_10") (pintype "input"))
      (node (ref "IC7") (pin "11") (pinfunction "V-_11") (pintype "power_in"))
      (node (ref "IC7") (pin "12") (pinfunction "+IN_12") (pintype "input"))
      (node (ref "IC7") (pin "3") (pinfunction "+IN_3") (pintype "input"))
      (node (ref "IC7") (pin "5") (pinfunction "+IN_5") (pintype "input"))
      (node (ref "IC8") (pin "1") (pinfunction "C_1") (pintype "passive"))
      (node (ref "IC9") (pin "10") (pinfunction "+_10") (pintype "input"))
      (node (ref "IC9") (pin "12") (pinfunction "+_12") (pintype "input"))
      (node (ref "IC9") (pin "3") (pinfunction "+_3") (pintype "input"))
      (node (ref "IC9") (pin "5") (pinfunction "+_5") (pintype "input"))
      (node (ref "J1") (pin "GND") (pinfunction "GND_GND") (pintype "passive"))
      (node (ref "J2") (pin "GND") (pinfunction "GND_GND") (pintype "passive"))
      (node (ref "J3") (pin "GND") (pinfunction "GND_GND") (pintype "passive"))
      (node (ref "J4") (pin "GND") (pinfunction "GND_GND") (pintype "passive"))
      (node (ref "J5") (pin "GND") (pinfunction "GND_GND") (pintype "passive"))
      (node (ref "J6") (pin "GND") (pinfunction "GND_GND") (pintype "passive"))
      (node (ref "JP1") (pin "3") (pinfunction "3_3") (pintype "passive"))
      (node (ref "JP1") (pin "4") (pinfunction "4_4") (pintype "passive"))
      (node (ref "JP1") (pin "5") (pinfunction "5_5") (pintype "passive"))
      (node (ref "JP1") (pin "6") (pinfunction "6_6") (pintype "passive"))
      (node (ref "JP1") (pin "7") (pinfunction "7_7") (pintype "passive"))
      (node (ref "JP1") (pin "8") (pinfunction "8_8") (pintype "passive"))
      (node (ref "JP10") (pin "1") (pinfunction "1_1") (pintype "passive"))
      (node (ref "JP12") (pin "1") (pinfunction "1_1") (pintype "passive"))
      (node (ref "JP13") (pin "1") (pinfunction "1_1") (pintype "passive"))
      (node (ref "JP14") (pin "1") (pinfunction "1_1") (pintype "passive"))
      (node (ref "JP2") (pin "3") (pinfunction "3_3") (pintype "passive"))
      (node (ref "JP2") (pin "5") (pinfunction "5_5") (pintype "passive"))
      (node (ref "JP2") (pin "9") (pinfunction "9_9") (pintype "passive"))
      (node (ref "JP6") (pin "1") (pinfunction "1_1") (pintype "passive"))
      (node (ref "JP9") (pin "1") (pinfunction "1_1") (pintype "passive"))
      (node (ref "Q5") (pin "GND") (pinfunction "GND_GND") (pintype "bidirectional"))
      (node (ref "Q6") (pin "E") (pinfunction "E_E") (pintype "passive"))
      (node (ref "R19") (pin "P$1") (pinfunction "1_P$1") (pintype "passive"))
      (node (ref "R20") (pin "P$1") (pinfunction "1_P$1") (pintype "passive"))
      (node (ref "R33") (pin "1") (pinfunction "1_1") (pintype "passive"))
      (node (ref "R36") (pin "P$1") (pinfunction "1_P$1") (pintype "passive"))
      (node (ref "R38") (pin "P$1") (pinfunction "1_P$1") (pintype "passive"))
      (node (ref "SW1") (pin "C") (pinfunction "C_C") (pintype "passive"))
      (node (ref "SW1") (pin "D") (pinfunction "1_D") (pintype "passive"))
      (node (ref "UC1") (pin "20") (pinfunction "PB2/BOOT1_20") (pintype "bidirectional"))
      (node (ref "UC1") (pin "23") (pinfunction "VSS_1_23") (pintype "power_in"))
      (node (ref "UC1") (pin "35") (pinfunction "VSS_2_35") (pintype "power_in"))
      (node (ref "UC1") (pin "46") (pinfunction "PB9/TIM4_CH4_46") (pintype "input"))
      (node (ref "UC1") (pin "47") (pinfunction "VSS_3_47") (pintype "power_in"))
      (node (ref "UC1") (pin "8") (pinfunction "VSS_A_8") (pintype "power_in"))
    )
    (net (code "27") (name "JTCK") (class "Default")
      (node (ref "JP2") (pin "4") (pinfunction "4_4") (pintype "passive"))
      (node (ref "UC1") (pin "37") (pinfunction "PA14/JTCK/SWCLK_37") (pintype "bidirectional"))
    )
    (net (code "28") (name "JTDI") (class "Default")
      (node (ref "JP2") (pin "8") (pinfunction "8_8") (pintype "passive"))
      (node (ref "UC1") (pin "38") (pinfunction "PA15/JTDI_38") (pintype "bidirectional"))
    )
    (net (code "29") (name "JTDO") (class "Default")
      (node (ref "JP2") (pin "6") (pinfunction "6_6") (pintype "passive"))
      (node (ref "UC1") (pin "39") (pinfunction "PB3/JTDO_39") (pintype "bidirectional"))
    )
    (net (code "30") (name "JTMS") (class "Default")
      (node (ref "JP2") (pin "2") (pinfunction "2_2") (pintype "passive"))
      (node (ref "UC1") (pin "34") (pinfunction "PA13/JTMS/SWDIO_34") (pintype "bidirectional"))
    )
    (net (code "31") (name "Net-(C21-Pad1)") (class "Default")
      (node (ref "C21") (pin "1") (pinfunction "1_1") (pintype "passive"))
      (node (ref "R45") (pin "1") (pinfunction "1_1") (pintype "passive"))
      (node (ref "R46") (pin "2") (pinfunction "2_2") (pintype "passive"))
    )
    (net (code "32") (name "Net-(C24-Pad-)") (class "Default")
      (node (ref "C24") (pin "-") (pinfunction "-_-") (pintype "passive"))
      (node (ref "R50") (pin "2") (pinfunction "2_2") (pintype "passive"))
    )
    (net (code "33") (name "Net-(D1-PadA)") (class "Default")
      (node (ref "D1") (pin "A") (pinfunction "A_A") (pintype "passive"))
      (node (ref "JP1") (pin "1") (pinfunction "1_1") (pintype "passive"))
      (node (ref "JP1") (pin "2") (pinfunction "2_2") (pintype "passive"))
    )
    (net (code "34") (name "Net-(D2-PadC)") (class "Default")
      (node (ref "D2") (pin "C") (pinfunction "C_C") (pintype "passive"))
      (node (ref "JP1") (pin "10") (pinfunction "10_10") (pintype "passive"))
      (node (ref "JP1") (pin "9") (pinfunction "9_9") (pintype "passive"))
    )
    (net (code "35") (name "Net-(IC6-VIN)") (class "Default")
      (node (ref "C19") (pin "+") (pinfunction "+_+") (pintype "passive"))
      (node (ref "IC6") (pin "2") (pinfunction "VIN_2") (pintype "input"))
      (node (ref "R49") (pin "1") (pinfunction "1_1") (pintype "passive"))
    )
    (net (code "36") (name "Net-(IC7A--IN)") (class "Default")
      (node (ref "C16") (pin "1") (pinfunction "1_1") (pintype "passive"))
      (node (ref "IC7") (pin "2") (pinfunction "-IN_2") (pintype "input"))
      (node (ref "R34") (pin "1") (pinfunction "1_1") (pintype "passive"))
      (node (ref "R39") (pin "2") (pinfunction "2_2") (pintype "passive"))
      (node (ref "R41") (pin "2") (pinfunction "2_2") (pintype "passive"))
    )
    (net (code "37") (name "Net-(IC7B--IN)") (class "Default")
      (node (ref "C17") (pin "1") (pinfunction "1_1") (pintype "passive"))
      (node (ref "IC7") (pin "6") (pinfunction "-IN_6") (pintype "input"))
      (node (ref "R21") (pin "P$1") (pinfunction "1_P$1") (pintype "passive"))
      (node (ref "R35") (pin "1") (pinfunction "1_1") (pintype "passive"))
      (node (ref "R40") (pin "2") (pinfunction "2_2") (pintype "passive"))
      (node (ref "R42") (pin "2") (pinfunction "2_2") (pintype "passive"))
    )
    (net (code "38") (name "Net-(IC7C--IN)") (class "Default")
      (node (ref "C14") (pin "1") (pinfunction "1_1") (pintype "passive"))
      (node (ref "IC7") (pin "9") (pinfunction "-IN_9") (pintype "input"))
      (node (ref "R26") (pin "1") (pinfunction "1_1") (pintype "passive"))
      (node (ref "R31") (pin "2") (pinfunction "2_2") (pintype "passive"))
      (node (ref "R32") (pin "2") (pinfunction "2_2") (pintype "passive"))
    )
    (net (code "39") (name "Net-(IC7D--IN)") (class "Default")
      (node (ref "C13") (pin "1") (pinfunction "1_1") (pintype "passive"))
      (node (ref "IC7") (pin "13") (pinfunction "-IN_13") (pintype "input"))
      (node (ref "R25") (pin "1") (pinfunction "1_1") (pintype "passive"))
      (node (ref "R28") (pin "2") (pinfunction "2_2") (pintype "passive"))
      (node (ref "R30") (pin "2") (pinfunction "2_2") (pintype "passive"))
      (node (ref "R37") (pin "P$1") (pinfunction "1_P$1") (pintype "passive"))
    )
    (net (code "40") (name "Net-(IC9A--)") (class "Default")
      (node (ref "IC9") (pin "2") (pinfunction "-_2") (pintype "input"))
      (node (ref "R21") (pin "P$3") (pinfunction "3_P$3") (pintype "passive"))
      (node (ref "R52") (pin "1") (pinfunction "1_1") (pintype "passive"))
    )
    (net (code "41") (name "Net-(IC9A-OUT)") (class "Default")
      (node (ref "IC9") (pin "1") (pinfunction "OUT_1") (pintype "output"))
      (node (ref "R42") (pin "1") (pinfunction "1_1") (pintype "passive"))
      (node (ref "R52") (pin "2") (pinfunction "2_2") (pintype "passive"))
    )
    (net (code "42") (name "Net-(IC9B--)") (class "Default")
      (node (ref "IC9") (pin "6") (pinfunction "-_6") (pintype "input"))
      (node (ref "R53") (pin "1") (pinfunction "1_1") (pintype "passive"))
      (node (ref "R54") (pin "2") (pinfunction "2_2") (pintype "passive"))
    )
    (net (code "43") (name "Net-(IC9B-OUT)") (class "Default")
      (node (ref "IC9") (pin "7") (pinfunction "OUT_7") (pintype "output"))
      (node (ref "R41") (pin "1") (pinfunction "1_1") (pintype "passive"))
      (node (ref "R53") (pin "2") (pinfunction "2_2") (pintype "passive"))
    )
    (net (code "44") (name "Net-(IC9C--)") (class "Default")
      (node (ref "IC9") (pin "9") (pinfunction "-_9") (pintype "input"))
      (node (ref "R44") (pin "1") (pinfunction "1_1") (pintype "passive"))
      (node (ref "R47") (pin "2") (pinfunction "2_2") (pintype "passive"))
    )
    (net (code "45") (name "Net-(IC9C-OUT)") (class "Default")
      (node (ref "IC9") (pin "8") (pinfunction "OUT_8") (pintype "output"))
      (node (ref "R31") (pin "1") (pinfunction "1_1") (pintype "passive"))
      (node (ref "R44") (pin "2") (pinfunction "2_2") (pintype "passive"))
    )
    (net (code "46") (name "Net-(IC9D--)") (class "Default")
      (node (ref "IC9") (pin "13") (pinfunction "-_13") (pintype "input"))
      (node (ref "R37") (pin "P$3") (pinfunction "3_P$3") (pintype "passive"))
      (node (ref "R43") (pin "1") (pinfunction "1_1") (pintype "passive"))
    )
    (net (code "47") (name "Net-(IC9D-OUT)") (class "Default")
      (node (ref "IC9") (pin "14") (pinfunction "OUT_14") (pintype "output"))
      (node (ref "R30") (pin "1") (pinfunction "1_1") (pintype "passive"))
      (node (ref "R43") (pin "2") (pinfunction "2_2") (pintype "passive"))
    )
    (net (code "48") (name "Net-(IC10A--IN)") (class "Default")
      (node (ref "C29") (pin "1") (pinfunction "1_1") (pintype "passive"))
      (node (ref "IC10") (pin "2") (pinfunction "-IN_2") (pintype "input"))
      (node (ref "R50") (pin "1") (pinfunction "1_1") (pintype "passive"))
      (node (ref "R56") (pin "2") (pinfunction "2_2") (pintype "passive"))
    )
    (net (code "49") (name "Net-(IC10A-OUT)") (class "Default")
      (node (ref "C29") (pin "2") (pinfunction "2_2") (pintype "passive"))
      (node (ref "IC10") (pin "1") (pinfunction "OUT_1") (pintype "output"))
      (node (ref "R55") (pin "2") (pinfunction "2_2") (pintype "passive"))
    )
    (net (code "50") (name "Net-(IC10B-+IN)") (class "Default")
      (node (ref "C22") (pin "1") (pinfunction "1_1") (pintype "passive"))
      (node (ref "IC10") (pin "5") (pinfunction "+IN_5") (pintype "input"))
      (node (ref "R46") (pin "1") (pinfunction "1_1") (pintype "passive"))
    )
    (net (code "51") (name "Net-(IC10B--IN)") (class "Default")
      (node (ref "C21") (pin "2") (pinfunction "2_2") (pintype "passive"))
      (node (ref "C24") (pin "+") (pinfunction "+_+") (pintype "passive"))
      (node (ref "IC10") (pin "6") (pinfunction "-IN_6") (pintype "input"))
      (node (ref "IC10") (pin "7") (pinfunction "OUT_7") (pintype "output"))
    )
    (net (code "52") (name "Net-(J1-PadTIP)") (class "Default")
      (node (ref "J1") (pin "TIP") (pinfunction "TIP_TIP") (pintype "passive"))
      (node (ref "R29") (pin "1") (pinfunction "1_1") (pintype "passive"))
    )
    (net (code "53") (name "Net-(J2-PadTIP)") (class "Default")
      (node (ref "J2") (pin "TIP") (pinfunction "TIP_TIP") (pintype "passive"))
      (node (ref "R54") (pin "1") (pinfunction "1_1") (pintype "passive"))
    )
    (net (code "54") (name "Net-(J3-PadTIP)") (class "Default")
      (node (ref "J3") (pin "TIP") (pinfunction "TIP_TIP") (pintype "passive"))
      (node (ref "R24") (pin "1") (pinfunction "1_1") (pintype "passive"))
    )
    (net (code "55") (name "Net-(J4-PadTIP)") (class "Default")
      (node (ref "J4") (pin "TIP") (pinfunction "TIP_TIP") (pintype "passive"))
      (node (ref "R48") (pin "1") (pinfunction "1_1") (pintype "passive"))
    )
    (net (code "56") (name "Net-(J5-PadTIP)") (class "Default")
      (node (ref "J5") (pin "TIP") (pinfunction "TIP_TIP") (pintype "passive"))
      (node (ref "R47") (pin "1") (pinfunction "1_1") (pintype "passive"))
    )
    (net (code "57") (name "Net-(J6-PadTIP)") (class "Default")
      (node (ref "J6") (pin "TIP") (pinfunction "TIP_TIP") (pintype "passive"))
      (node (ref "R55") (pin "1") (pinfunction "1_1") (pintype "passive"))
      (node (ref "R56") (pin "1") (pinfunction "1_1") (pintype "passive"))
    )
    (net (code "58") (name "Net-(Q6-PadB)") (class "Default")
      (node (ref "Q6") (pin "B") (pinfunction "B_B") (pintype "passive"))
      (node (ref "R29") (pin "2") (pinfunction "2_2") (pintype "passive"))
    )
    (net (code "59") (name "Net-(R20-2)") (class "Default")
      (node (ref "R20") (pin "P$2") (pinfunction "2_P$2") (pintype "passive"))
      (node (ref "R39") (pin "1") (pinfunction "1_1") (pintype "passive"))
    )
    (net (code "60") (name "Net-(R21-2)") (class "Default")
      (node (ref "R21") (pin "P$2") (pinfunction "2_P$2") (pintype "passive"))
      (node (ref "R24") (pin "2") (pinfunction "2_2") (pintype "passive"))
    )
    (net (code "61") (name "Net-(R36-2)") (class "Default")
      (node (ref "R28") (pin "1") (pinfunction "1_1") (pintype "passive"))
      (node (ref "R36") (pin "P$2") (pinfunction "2_P$2") (pintype "passive"))
    )
    (net (code "62") (name "Net-(R37-2)") (class "Default")
      (node (ref "R37") (pin "P$2") (pinfunction "2_P$2") (pintype "passive"))
      (node (ref "R48") (pin "2") (pinfunction "2_2") (pintype "passive"))
    )
    (net (code "63") (name "Net-(R38-2)") (class "Default")
      (node (ref "R32") (pin "1") (pinfunction "1_1") (pintype "passive"))
      (node (ref "R38") (pin "P$2") (pinfunction "2_P$2") (pintype "passive"))
    )
    (net (code "64") (name "Net-(UC1-PD0-OSC_IN)") (class "Default")
      (node (ref "Q5") (pin "X1") (pinfunction "X1_X1") (pintype "bidirectional"))
      (node (ref "UC1") (pin "5") (pinfunction "PD0-OSC_IN_5") (pintype "input"))
    )
    (net (code "65") (name "Net-(UC1-PD1-OSC_OUT)") (class "Default")
      (node (ref "Q5") (pin "X2") (pinfunction "X2_X2") (pintype "bidirectional"))
      (node (ref "UC1") (pin "6") (pinfunction "PD1-OSC_OUT_6") (pintype "input"))
    )
    (net (code "66") (name "PARAM1_CV") (class "Default")
      (node (ref "C13") (pin "2") (pinfunction "2_2") (pintype "passive"))
      (node (ref "IC4") (pin "1") (pinfunction "CH0_1") (pintype "bidirectional"))
      (node (ref "IC7") (pin "14") (pinfunction "OUT_14") (pintype "output"))
      (node (ref "R25") (pin "2") (pinfunction "2_2") (pintype "passive"))
    )
    (net (code "67") (name "PARAM2_CV") (class "Default")
      (node (ref "C14") (pin "2") (pinfunction "2_2") (pintype "passive"))
      (node (ref "IC4") (pin "2") (pinfunction "CH1_2") (pintype "bidirectional"))
      (node (ref "IC7") (pin "8") (pinfunction "OUT_8") (pintype "output"))
      (node (ref "R26") (pin "2") (pinfunction "2_2") (pintype "passive"))
    )
    (net (code "68") (name "PITCH_CV") (class "Default")
      (node (ref "C16") (pin "2") (pinfunction "2_2") (pintype "passive"))
      (node (ref "IC4") (pin "3") (pinfunction "CH2_3") (pintype "bidirectional"))
      (node (ref "IC7") (pin "1") (pinfunction "OUT_1") (pintype "output"))
      (node (ref "R34") (pin "2") (pinfunction "2_2") (pintype "passive"))
    )
    (net (code "69") (name "RESET") (class "Default")
      (node (ref "JP2") (pin "10") (pinfunction "10_10") (pintype "passive"))
      (node (ref "R22") (pin "1") (pinfunction "1_1") (pintype "passive"))
      (node (ref "UC1") (pin "7") (pinfunction "NRST_7") (pintype "input"))
    )
    (net (code "70") (name "RX") (class "Default")
      (node (ref "UC1") (pin "31") (pinfunction "PA10/USART1_RX/TIM1_CH3_31") (pintype "bidirectional"))
    )
    (net (code "71") (name "TX") (class "Default")
      (node (ref "UC1") (pin "30") (pinfunction "PA9/USART1_TX/TIM1_CH2_30") (pintype "input"))
    )
    (net (code "72") (name "VCC") (class "Default")
      (node (ref "C23") (pin "1") (pinfunction "1_1") (pintype "passive"))
      (node (ref "C25") (pin "+") (pinfunction "+_+") (pintype "passive"))
      (node (ref "C28") (pin "1") (pinfunction "1_1") (pintype "passive"))
      (node (ref "D1") (pin "C") (pinfunction "C_C") (pintype "passive"))
      (node (ref "IC10") (pin "8") (pinfunction "V+_8") (pintype "power_in"))
      (node (ref "IC9") (pin "4") (pinfunction "+_4") (pintype "bidirectional"))
      (node (ref "R49") (pin "2") (pinfunction "2_2") (pintype "passive"))
    )
    (net (code "73") (name "VEE") (class "Default")
      (node (ref "C20") (pin "2") (pinfunction "2_2") (pintype "passive"))
      (node (ref "C27") (pin "2") (pinfunction "2_2") (pintype "passive"))
      (node (ref "C30") (pin "-") (pinfunction "-_-") (pintype "passive"))
      (node (ref "D2") (pin "A") (pinfunction "A_A") (pintype "passive"))
      (node (ref "IC10") (pin "4") (pinfunction "V-_4") (pintype "power_in"))
      (node (ref "IC9") (pin "11") (pinfunction "-_11") (pintype "bidirectional"))
      (node (ref "R51") (pin "1") (pinfunction "1_1") (pintype "passive"))
    )
    (net (code "74") (name "unconnected-(J1-PadNORM)") (class "Default")
      (node (ref "J1") (pin "NORM") (pinfunction "NORM_NORM") (pintype "passive"))
    )
    (net (code "75") (name "unconnected-(J2-PadNORM)") (class "Default")
      (node (ref "J2") (pin "NORM") (pinfunction "NORM_NORM") (pintype "passive"))
    )
    (net (code "76") (name "unconnected-(J3-PadNORM)") (class "Default")
      (node (ref "J3") (pin "NORM") (pinfunction "NORM_NORM") (pintype "passive"))
    )
    (net (code "77") (name "unconnected-(J4-PadNORM)") (class "Default")
      (node (ref "J4") (pin "NORM") (pinfunction "NORM_NORM") (pintype "passive"))
    )
    (net (code "78") (name "unconnected-(J5-PadNORM)") (class "Default")
      (node (ref "J5") (pin "NORM") (pinfunction "NORM_NORM") (pintype "passive"))
    )
    (net (code "79") (name "unconnected-(J6-PadNORM)") (class "Default")
      (node (ref "J6") (pin "NORM") (pinfunction "NORM_NORM") (pintype "passive"))
    )
    (net (code "80") (name "unconnected-(JP2-Pad7)") (class "Default")
      (node (ref "JP2") (pin "7") (pinfunction "7_7") (pintype "passive"))
    )
    (net (code "81") (name "unconnected-(UC1-PA0_WKUP{slash}USART2_CTS{slash}ADC12_IN0{slash}TIM2_CH1_ETR-Pad10)") (class "Default")
      (node (ref "UC1") (pin "10") (pinfunction "PA0_WKUP/USART2_CTS/ADC12_IN0/TIM2_CH1_ETR_10") (pintype "bidirectional"))
    )
    (net (code "82") (name "unconnected-(UC1-PA1{slash}USART2_RTS{slash}ADC12_IN1{slash}TIM2_CH2-Pad11)") (class "Default")
      (node (ref "UC1") (pin "11") (pinfunction "PA1/USART2_RTS/ADC12_IN1/TIM2_CH2_11") (pintype "bidirectional"))
    )
    (net (code "83") (name "unconnected-(UC1-PA2{slash}USART2_TX{slash}ADC12_IN2{slash}TIM2_CH3-Pad12)") (class "Default")
      (node (ref "UC1") (pin "12") (pinfunction "PA2/USART2_TX/ADC12_IN2/TIM2_CH3_12") (pintype "bidirectional"))
    )
    (net (code "84") (name "unconnected-(UC1-PA8{slash}USART1_CK{slash}TIM1_CH1{slash}MCO-Pad29)") (class "Default")
      (node (ref "UC1") (pin "29") (pinfunction "PA8/USART1_CK/TIM1_CH1/MCO_29") (pintype "bidirectional"))
    )
    (net (code "85") (name "unconnected-(UC1-PA11{slash}USART1_CTS{slash}CAN_RX{slash}TIM1_CH4{slash}USBDM-Pad32)") (class "Default")
      (node (ref "UC1") (pin "32") (pinfunction "PA11/USART1_CTS/CAN_RX/TIM1_CH4/USBDM_32") (pintype "bidirectional"))
    )
    (net (code "86") (name "unconnected-(UC1-PA12{slash}USART1_RTS{slash}CAN_TX{slash}TIM1_ETR{slash}USBDP-Pad33)") (class "Default")
      (node (ref "UC1") (pin "33") (pinfunction "PA12/USART1_RTS/CAN_TX/TIM1_ETR/USBDP_33") (pintype "bidirectional"))
    )
    (net (code "87") (name "unconnected-(UC1-PB4{slash}NJTRST-Pad40)") (class "Default")
      (node (ref "UC1") (pin "40") (pinfunction "PB4/NJTRST_40") (pintype "bidirectional"))
    )
    (net (code "88") (name "unconnected-(UC1-PB14{slash}SPI2_MISO{slash}USART3_RTS{slash}TIM1_CH2N-Pad27)") (class "Default")
      (node (ref "UC1") (pin "27") (pinfunction "PB14/SPI2_MISO/USART3_RTS/TIM1_CH2N_27") (pintype "input"))
    )
  )
)
